# 1-Schematic_dram_sram_cell.net
KiCad netlist of a schematic drawn in EasyEDA
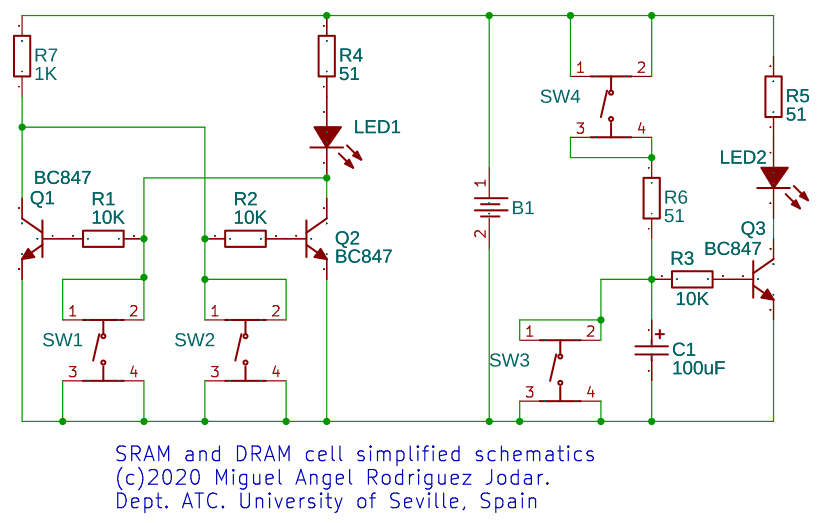
[diagram p0: schematic sheet]

(export (version "E")
  (design (tool "Eeschema 10.0.6"))
  (components
    (comp (ref "B1")
      (value "CR2032-BS-6-1")
      (fields (field (name "BOM_Supplier Part") "C70377"))
      (libsource (lib "") (part "CR2032-BS-6-1"))
    )
    (comp (ref "C1")
      (value "100uF")
      (fields
        (field (name "BOM_Manufacturer Part") "TAJB107K006RNJ")
        (field (name "BOM_Supplier Part") "C16133")
      )
      (libsource (lib "") (part "TAJB107K006RNJ"))
    )
    (comp (ref "LED1")
      (value "KT-0603R")
      (fields (field (name "BOM_Supplier Part") "C2286"))
      (libsource (lib "") (part "KT-0603R"))
    )
    (comp (ref "LED2")
      (value "KT-0603R")
      (fields (field (name "BOM_Supplier Part") "C2286"))
      (libsource (lib "") (part "KT-0603R"))
    )
    (comp (ref "Q1")
      (value "BC847")
      (fields (field (name "BOM_Supplier Part") "C8574"))
      (libsource (lib "") (part "BC847_1"))
    )
    (comp (ref "Q2")
      (value "BC847")
      (fields (field (name "BOM_Supplier Part") "C8574"))
      (libsource (lib "") (part "BC847"))
    )
    (comp (ref "Q3")
      (value "BC847")
      (fields (field (name "BOM_Supplier Part") "C8574"))
      (libsource (lib "") (part "BC847"))
    )
    (comp (ref "R1")
      (value "10K")
      (fields
        (field (name "BOM_Manufacturer Part") "0603WAF1002T5E")
        (field (name "BOM_Supplier Part") "C25804")
      )
      (libsource (lib "") (part "0603WAF1002T5E"))
    )
    (comp (ref "R2")
      (value "10K")
      (fields
        (field (name "BOM_Manufacturer Part") "0603WAF1002T5E")
        (field (name "BOM_Supplier Part") "C25804")
      )
      (libsource (lib "") (part "0603WAF1002T5E"))
    )
    (comp (ref "R3")
      (value "10K")
      (fields
        (field (name "BOM_Manufacturer Part") "0603WAF1002T5E")
        (field (name "BOM_Supplier Part") "C25804")
      )
      (libsource (lib "") (part "0603WAF1002T5E"))
    )
    (comp (ref "R4")
      (value "51")
      (fields
        (field (name "BOM_Manufacturer Part") "0603WAF510JT5E")
        (field (name "BOM_Supplier Part") "C23197")
      )
      (libsource (lib "") (part "0603WAF510JT5E"))
    )
    (comp (ref "R5")
      (value "51")
      (fields
        (field (name "BOM_Manufacturer Part") "0603WAF510JT5E")
        (field (name "BOM_Supplier Part") "C23197")
      )
      (libsource (lib "") (part "0603WAF510JT5E"))
    )
    (comp (ref "R6")
      (value "51")
      (fields
        (field (name "BOM_Manufacturer Part") "0603WAF510JT5E")
        (field (name "BOM_Supplier Part") "C23197")
      )
      (libsource (lib "") (part "0603WAF510JT5E"))
    )
    (comp (ref "R7")
      (value "1K")
      (fields
        (field (name "BOM_Manufacturer Part") "0603WAF1001T5E")
        (field (name "BOM_Supplier Part") "C21190")
      )
      (libsource (lib "") (part "0603WAF1001T5E"))
    )
    (comp (ref "SW1")
      (value "TS-1187A-C-E-B")
      (fields (field (name "BOM_Supplier Part") "C318887"))
      (libsource (lib "") (part "TS-1187A-C-E-B"))
    )
    (comp (ref "SW2")
      (value "TS-1187A-C-E-B")
      (fields (field (name "BOM_Supplier Part") "C318887"))
      (libsource (lib "") (part "TS-1187A-C-E-B"))
    )
    (comp (ref "SW3")
      (value "TS-1187A-C-E-B")
      (fields (field (name "BOM_Supplier Part") "C318887"))
      (libsource (lib "") (part "TS-1187A-C-E-B"))
    )
    (comp (ref "SW4")
      (value "TS-1187A-C-E-B")
      (fields (field (name "BOM_Supplier Part") "C318887"))
      (libsource (lib "") (part "TS-1187A-C-E-B"))
    )
  )
  (nets
    (net (code "1") (name "Net-(LED1-A)") (class "Default")
      (node (ref "LED1") (pin "1") (pinfunction "A_1") (pintype "unspecified"))
      (node (ref "R4") (pin "1") (pinfunction "1_1") (pintype "input"))
    )
    (net (code "2") (name "Net-(LED1-K)") (class "Default")
      (node (ref "LED1") (pin "2") (pinfunction "K_2") (pintype "unspecified"))
      (node (ref "Q2") (pin "3") (pinfunction "C_3") (pintype "unspecified"))
      (node (ref "R1") (pin "2") (pinfunction "2_2") (pintype "input"))
      (node (ref "SW1") (pin "1") (pinfunction "A_1") (pintype "unspecified"))
      (node (ref "SW1") (pin "2") (pinfunction "B_2") (pintype "unspecified"))
    )
    (net (code "3") (name "Net-(LED2-A)") (class "Default")
      (node (ref "LED2") (pin "1") (pinfunction "A_1") (pintype "unspecified"))
      (node (ref "R5") (pin "1") (pinfunction "1_1") (pintype "input"))
    )
    (net (code "4") (name "Net-(LED2-K)") (class "Default")
      (node (ref "LED2") (pin "2") (pinfunction "K_2") (pintype "unspecified"))
      (node (ref "Q3") (pin "3") (pinfunction "C_3") (pintype "unspecified"))
    )
    (net (code "5") (name "Net-(Q1-B)") (class "Default")
      (node (ref "Q1") (pin "1") (pinfunction "B_1") (pintype "unspecified"))
      (node (ref "R1") (pin "1") (pinfunction "1_1") (pintype "input"))
    )
    (net (code "6") (name "Net-(Q1-C)") (class "Default")
      (node (ref "Q1") (pin "3") (pinfunction "C_3") (pintype "unspecified"))
      (node (ref "R2") (pin "1") (pinfunction "1_1") (pintype "input"))
      (node (ref "R7") (pin "1") (pinfunction "1_1") (pintype "input"))
      (node (ref "SW2") (pin "1") (pinfunction "A_1") (pintype "unspecified"))
      (node (ref "SW2") (pin "2") (pinfunction "B_2") (pintype "unspecified"))
    )
    (net (code "7") (name "Net-(Q1-E)") (class "Default")
      (node (ref "B1") (pin "2") (pinfunction "2_2") (pintype "input"))
      (node (ref "C1") (pin "2") (pinfunction "2_2") (pintype "input"))
      (node (ref "Q1") (pin "2") (pinfunction "E_2") (pintype "unspecified"))
      (node (ref "Q2") (pin "2") (pinfunction "E_2") (pintype "unspecified"))
      (node (ref "Q3") (pin "2") (pinfunction "E_2") (pintype "unspecified"))
      (node (ref "SW1") (pin "3") (pinfunction "C_3") (pintype "unspecified"))
      (node (ref "SW1") (pin "4") (pinfunction "D_4") (pintype "unspecified"))
      (node (ref "SW2") (pin "3") (pinfunction "C_3") (pintype "unspecified"))
      (node (ref "SW2") (pin "4") (pinfunction "D_4") (pintype "unspecified"))
      (node (ref "SW3") (pin "3") (pinfunction "C_3") (pintype "unspecified"))
      (node (ref "SW3") (pin "4") (pinfunction "D_4") (pintype "unspecified"))
    )
    (net (code "8") (name "Net-(Q2-B)") (class "Default")
      (node (ref "Q2") (pin "1") (pinfunction "B_1") (pintype "unspecified"))
      (node (ref "R2") (pin "2") (pinfunction "2_2") (pintype "input"))
    )
    (net (code "9") (name "Net-(Q3-B)") (class "Default")
      (node (ref "Q3") (pin "1") (pinfunction "B_1") (pintype "unspecified"))
      (node (ref "R3") (pin "2") (pinfunction "2_2") (pintype "input"))
    )
    (net (code "10") (name "Net-(SW3-A)") (class "Default")
      (node (ref "C1") (pin "1") (pinfunction "1_1") (pintype "input"))
      (node (ref "R3") (pin "1") (pinfunction "1_1") (pintype "input"))
      (node (ref "R6") (pin "1") (pinfunction "1_1") (pintype "input"))
      (node (ref "SW3") (pin "1") (pinfunction "A_1") (pintype "unspecified"))
      (node (ref "SW3") (pin "2") (pinfunction "B_2") (pintype "unspecified"))
    )
    (net (code "11") (name "Net-(SW4-A)") (class "Default")
      (node (ref "B1") (pin "1") (pinfunction "1_1") (pintype "input"))
      (node (ref "R4") (pin "2") (pinfunction "2_2") (pintype "input"))
      (node (ref "R5") (pin "2") (pinfunction "2_2") (pintype "input"))
      (node (ref "R7") (pin "2") (pinfunction "2_2") (pintype "input"))
      (node (ref "SW4") (pin "1") (pinfunction "A_1") (pintype "unspecified"))
      (node (ref "SW4") (pin "2") (pinfunction "B_2") (pintype "unspecified"))
    )
    (net (code "12") (name "Net-(SW4-C)") (class "Default")
      (node (ref "R6") (pin "2") (pinfunction "2_2") (pintype "input"))
      (node (ref "SW4") (pin "3") (pinfunction "C_3") (pintype "unspecified"))
      (node (ref "SW4") (pin "4") (pinfunction "D_4") (pintype "unspecified"))
    )
  )
)
